# Power_ATX.net
KiCad netlist of a schematic drawn in Altium Designer
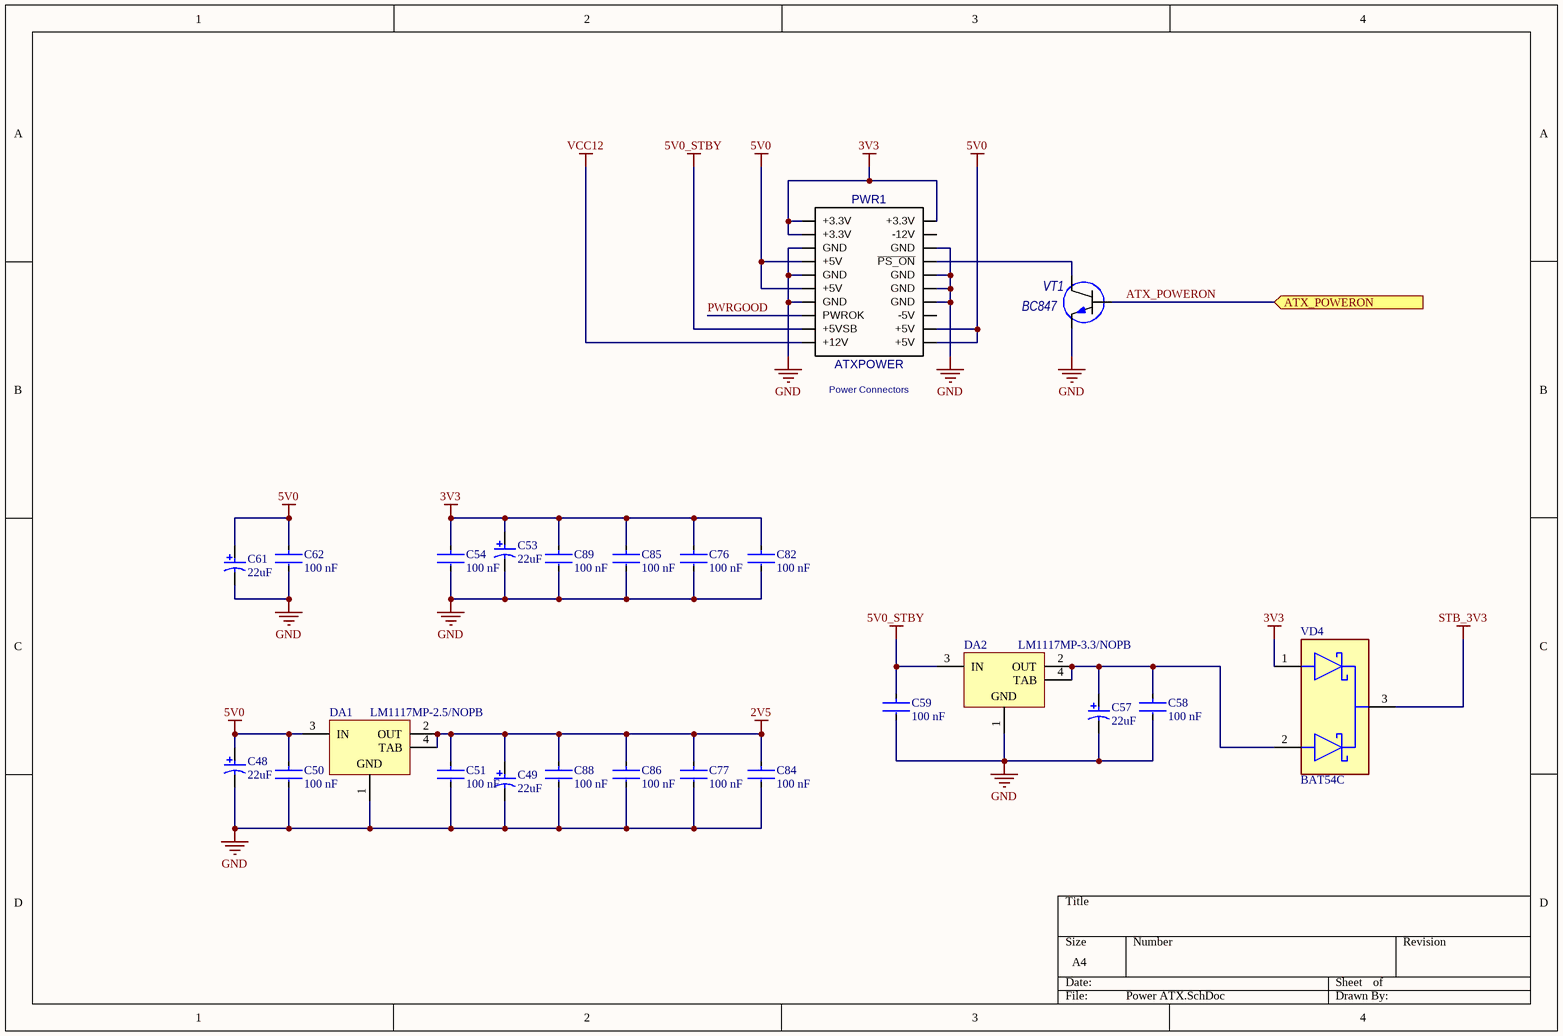
[diagram p0: Power ATX.SchDoc]

(export (version "E")
  (design (tool "Eeschema 10.0.6"))
  (components
    (comp (ref "C48")
      (value "TAJB226K016RNJ")
      (footprint "AVX-TAJ-B-2_M")
      (description "Standard Tantalum, 22 uF, +/- 10%, 16 V, -55 to 125 degC, 2-Pin SMD (1210), RoHS, Tape and Reel")
      (fields (field (name "CAPACITANCE") "22uF") (field (name "MANUFACTURER") "Kyocera AVX"))
      (libsource (lib "SchLib") (part "CMP-2100-03689-1"))
    )
    (comp (ref "C49")
      (value "TAJB226K016RNJ")
      (footprint "AVX-TAJ-B-2_M")
      (description "Standard Tantalum, 22 uF, +/- 10%, 16 V, -55 to 125 degC, 2-Pin SMD (1210), RoHS, Tape and Reel")
      (fields (field (name "CAPACITANCE") "22uF") (field (name "MANUFACTURER") "Kyocera AVX"))
      (libsource (lib "SchLib") (part "CMP-2100-03689-1"))
    )
    (comp (ref "C50")
      (value "CC0805KRX7R9BB104")
      (footprint "FP-CC0805-0_85-IPC_A")
      (description "CAP CER 0.1UF 50V X7R 0805")
      (fields (field (name "CAPACITANCE") "100 nF") (field (name "MANUFACTURER") "Yageo"))
      (libsource (lib "SchLib") (part "CMP-2100-03606-3"))
    )
    (comp (ref "C51")
      (value "CC0805KRX7R9BB104")
      (footprint "FP-CC0805-0_85-IPC_A")
      (description "CAP CER 0.1UF 50V X7R 0805")
      (fields (field (name "CAPACITANCE") "100 nF") (field (name "MANUFACTURER") "Yageo"))
      (libsource (lib "SchLib") (part "CMP-2100-03606-3"))
    )
    (comp (ref "C53")
      (value "TAJB226K016RNJ")
      (footprint "AVX-TAJ-B-2_M")
      (description "Standard Tantalum, 22 uF, +/- 10%, 16 V, -55 to 125 degC, 2-Pin SMD (1210), RoHS, Tape and Reel")
      (fields (field (name "CAPACITANCE") "22uF") (field (name "MANUFACTURER") "Kyocera AVX"))
      (libsource (lib "SchLib") (part "CMP-2100-03689-1"))
    )
    (comp (ref "C54")
      (value "CC0805KRX7R9BB104")
      (footprint "FP-CC0805-0_85-IPC_A")
      (description "CAP CER 0.1UF 50V X7R 0805")
      (fields (field (name "CAPACITANCE") "100 nF") (field (name "MANUFACTURER") "Yageo"))
      (libsource (lib "SchLib") (part "CMP-2100-03606-3"))
    )
    (comp (ref "C57")
      (value "TAJB226K016RNJ")
      (footprint "AVX-TAJ-B-2_M")
      (description "Standard Tantalum, 22 uF, +/- 10%, 16 V, -55 to 125 degC, 2-Pin SMD (1210), RoHS, Tape and Reel")
      (fields (field (name "CAPACITANCE") "22uF") (field (name "MANUFACTURER") "Kyocera AVX"))
      (libsource (lib "SchLib") (part "CMP-2100-03689-1"))
    )
    (comp (ref "C58")
      (value "CC0805KRX7R9BB104")
      (footprint "FP-CC0805-0_85-IPC_A")
      (description "CAP CER 0.1UF 50V X7R 0805")
      (fields (field (name "MANUFACTURER") "Yageo") (field (name "CAPACITANCE") "100 nF"))
      (libsource (lib "SchLib") (part "CMP-2100-03606-3"))
    )
    (comp (ref "C59")
      (value "CC0805KRX7R9BB104")
      (footprint "FP-CC0805-0_85-IPC_A")
      (description "CAP CER 0.1UF 50V X7R 0805")
      (fields (field (name "MANUFACTURER") "Yageo") (field (name "CAPACITANCE") "100 nF"))
      (libsource (lib "SchLib") (part "CMP-2100-03606-3"))
    )
    (comp (ref "C61")
      (value "TAJB226K016RNJ")
      (footprint "AVX-TAJ-B-2_M")
      (description "Standard Tantalum, 22 uF, +/- 10%, 16 V, -55 to 125 degC, 2-Pin SMD (1210), RoHS, Tape and Reel")
      (fields (field (name "CAPACITANCE") "22uF") (field (name "MANUFACTURER") "Kyocera AVX"))
      (libsource (lib "SchLib") (part "CMP-2100-03689-1"))
    )
    (comp (ref "C62")
      (value "CC0805KRX7R9BB104")
      (footprint "FP-CC0805-0_85-IPC_A")
      (description "CAP CER 0.1UF 50V X7R 0805")
      (fields (field (name "CAPACITANCE") "100 nF") (field (name "MANUFACTURER") "Yageo"))
      (libsource (lib "SchLib") (part "CMP-2100-03606-3"))
    )
    (comp (ref "C76")
      (value "CC0805KRX7R9BB104")
      (footprint "FP-CC0805-0_85-IPC_A")
      (description "CAP CER 0.1UF 50V X7R 0805")
      (fields (field (name "CAPACITANCE") "100 nF") (field (name "MANUFACTURER") "Yageo"))
      (libsource (lib "SchLib") (part "CMP-2100-03606-3"))
    )
    (comp (ref "C77")
      (value "CC0805KRX7R9BB104")
      (footprint "FP-CC0805-0_85-IPC_A")
      (description "CAP CER 0.1UF 50V X7R 0805")
      (fields (field (name "CAPACITANCE") "100 nF") (field (name "MANUFACTURER") "Yageo"))
      (libsource (lib "SchLib") (part "CMP-2100-03606-3"))
    )
    (comp (ref "C82")
      (value "CC0805KRX7R9BB104")
      (footprint "FP-CC0805-0_85-IPC_A")
      (description "CAP CER 0.1UF 50V X7R 0805")
      (fields (field (name "CAPACITANCE") "100 nF") (field (name "MANUFACTURER") "Yageo"))
      (libsource (lib "SchLib") (part "CMP-2100-03606-3"))
    )
    (comp (ref "C84")
      (value "CC0805KRX7R9BB104")
      (footprint "FP-CC0805-0_85-IPC_A")
      (description "CAP CER 0.1UF 50V X7R 0805")
      (fields (field (name "CAPACITANCE") "100 nF") (field (name "MANUFACTURER") "Yageo"))
      (libsource (lib "SchLib") (part "CMP-2100-03606-3"))
    )
    (comp (ref "C85")
      (value "CC0805KRX7R9BB104")
      (footprint "FP-CC0805-0_85-IPC_A")
      (description "CAP CER 0.1UF 50V X7R 0805")
      (fields (field (name "CAPACITANCE") "100 nF") (field (name "MANUFACTURER") "Yageo"))
      (libsource (lib "SchLib") (part "CMP-2100-03606-3"))
    )
    (comp (ref "C86")
      (value "CC0805KRX7R9BB104")
      (footprint "FP-CC0805-0_85-IPC_A")
      (description "CAP CER 0.1UF 50V X7R 0805")
      (fields (field (name "CAPACITANCE") "100 nF") (field (name "MANUFACTURER") "Yageo"))
      (libsource (lib "SchLib") (part "CMP-2100-03606-3"))
    )
    (comp (ref "C88")
      (value "CC0805KRX7R9BB104")
      (footprint "FP-CC0805-0_85-IPC_A")
      (description "CAP CER 0.1UF 50V X7R 0805")
      (fields (field (name "CAPACITANCE") "100 nF") (field (name "MANUFACTURER") "Yageo"))
      (libsource (lib "SchLib") (part "CMP-2100-03606-3"))
    )
    (comp (ref "C89")
      (value "CC0805KRX7R9BB104")
      (footprint "FP-CC0805-0_85-IPC_A")
      (description "CAP CER 0.1UF 50V X7R 0805")
      (fields (field (name "CAPACITANCE") "100 nF") (field (name "MANUFACTURER") "Yageo"))
      (libsource (lib "SchLib") (part "CMP-2100-03606-3"))
    )
    (comp (ref "DA1")
      (value "LM1117MP-2.5/NOPB")
      (footprint "DCY0004A_M")
      (description "800mA Low-Dropout Linear Regulator, 4-pin SOT-223, Pb-Free")
      (fields (field (name "MANUFACTURER") "TI National Semiconductor"))
      (libsource (lib "SchLib") (part "CMP-0062-01660-4"))
    )
    (comp (ref "DA2")
      (value "LM1117MP-3.3/NOPB")
      (footprint "DCY0004A_L")
      (description "800mA Low-Dropout Linear Regulator, 4-pin SOT-223, Pb-Free")
      (fields (field (name "MANUFACTURER") "TI National Semiconductor"))
      (libsource (lib "SchLib") (part "CMP-0062-01638-4"))
    )
    (comp (ref "PWR1") (value "ATXPOWER") (footprint "ATXPOWER") (libsource (lib "SchLib") (part "ATXPOWER")))
    (comp (ref "VD4")
      (value "BAT54C")
      (footprint "FP-MA03D-MFG")
      (description "DIODE ARRAY SCHOTTKY 30V SOT23-3")
      (fields (field (name "MANUFACTURER") "ON Semiconductor / Fairchild"))
      (libsource (lib "SchLib") (part "CMP-07162-000010-1"))
    )
    (comp (ref "VT1") (value "BC847") (footprint "SOT-23") (libsource (lib "SchLib") (part "BC847")))
  )
  (nets
    (net (code "1") (name "/ATX_POWERON") (class "Default")
      (node (ref "VT1") (pin "1") (pinfunction "base_1") (pintype "passive"))
    )
    (net (code "2") (name "/PWRGOOD") (class "Default")
      (node (ref "PWR1") (pin "8") (pinfunction "PWROK_8") (pintype "passive"))
    )
    (net (code "3") (name "2V5") (class "Default")
      (node (ref "C49") (pin "1") (pinfunction "1_1") (pintype "passive"))
      (node (ref "C51") (pin "1") (pinfunction "1_1") (pintype "passive"))
      (node (ref "C77") (pin "1") (pinfunction "1_1") (pintype "passive"))
      (node (ref "C84") (pin "1") (pinfunction "1_1") (pintype "passive"))
      (node (ref "C86") (pin "1") (pinfunction "1_1") (pintype "passive"))
      (node (ref "C88") (pin "1") (pinfunction "1_1") (pintype "passive"))
      (node (ref "DA1") (pin "2") (pinfunction "OUT_2") (pintype "power_in"))
      (node (ref "DA1") (pin "4") (pinfunction "TAB_4") (pintype "power_in"))
    )
    (net (code "4") (name "3V3") (class "Default")
      (node (ref "C53") (pin "1") (pinfunction "1_1") (pintype "passive"))
      (node (ref "C54") (pin "1") (pinfunction "1_1") (pintype "passive"))
      (node (ref "C76") (pin "1") (pinfunction "1_1") (pintype "passive"))
      (node (ref "C82") (pin "1") (pinfunction "1_1") (pintype "passive"))
      (node (ref "C85") (pin "1") (pinfunction "1_1") (pintype "passive"))
      (node (ref "C89") (pin "1") (pinfunction "1_1") (pintype "passive"))
      (node (ref "PWR1") (pin "1") (pinfunction "+3.3V_1") (pintype "passive"))
      (node (ref "PWR1") (pin "11") (pinfunction "+3.3V_11") (pintype "passive"))
      (node (ref "PWR1") (pin "2") (pinfunction "+3.3V_2") (pintype "passive"))
      (node (ref "VD4") (pin "1") (pinfunction "1_ANODE_1") (pintype "passive"))
    )
    (net (code "5") (name "5V0") (class "Default")
      (node (ref "C48") (pin "1") (pinfunction "1_1") (pintype "passive"))
      (node (ref "C50") (pin "1") (pinfunction "1_1") (pintype "passive"))
      (node (ref "C61") (pin "1") (pinfunction "1_1") (pintype "passive"))
      (node (ref "C62") (pin "1") (pinfunction "1_1") (pintype "passive"))
      (node (ref "DA1") (pin "3") (pinfunction "IN_3") (pintype "power_in"))
      (node (ref "PWR1") (pin "19") (pinfunction "+5V_19") (pintype "passive"))
      (node (ref "PWR1") (pin "20") (pinfunction "+5V_20") (pintype "passive"))
      (node (ref "PWR1") (pin "4") (pinfunction "+5V_4") (pintype "passive"))
      (node (ref "PWR1") (pin "6") (pinfunction "+5V_6") (pintype "passive"))
    )
    (net (code "6") (name "5V0_STBY") (class "Default")
      (node (ref "C59") (pin "1") (pinfunction "1_1") (pintype "passive"))
      (node (ref "DA2") (pin "3") (pinfunction "IN_3") (pintype "power_in"))
      (node (ref "PWR1") (pin "9") (pinfunction "+5VSB_9") (pintype "passive"))
    )
    (net (code "7") (name "GND") (class "Default")
      (node (ref "C48") (pin "2") (pinfunction "2_2") (pintype "passive"))
      (node (ref "C49") (pin "2") (pinfunction "2_2") (pintype "passive"))
      (node (ref "C50") (pin "2") (pinfunction "2_2") (pintype "passive"))
      (node (ref "C51") (pin "2") (pinfunction "2_2") (pintype "passive"))
      (node (ref "C53") (pin "2") (pinfunction "2_2") (pintype "passive"))
      (node (ref "C54") (pin "2") (pinfunction "2_2") (pintype "passive"))
      (node (ref "C57") (pin "2") (pinfunction "2_2") (pintype "passive"))
      (node (ref "C58") (pin "2") (pinfunction "2_2") (pintype "passive"))
      (node (ref "C59") (pin "2") (pinfunction "2_2") (pintype "passive"))
      (node (ref "C61") (pin "2") (pinfunction "2_2") (pintype "passive"))
      (node (ref "C62") (pin "2") (pinfunction "2_2") (pintype "passive"))
      (node (ref "C76") (pin "2") (pinfunction "2_2") (pintype "passive"))
      (node (ref "C77") (pin "2") (pinfunction "2_2") (pintype "passive"))
      (node (ref "C82") (pin "2") (pinfunction "2_2") (pintype "passive"))
      (node (ref "C84") (pin "2") (pinfunction "2_2") (pintype "passive"))
      (node (ref "C85") (pin "2") (pinfunction "2_2") (pintype "passive"))
      (node (ref "C86") (pin "2") (pinfunction "2_2") (pintype "passive"))
      (node (ref "C88") (pin "2") (pinfunction "2_2") (pintype "passive"))
      (node (ref "C89") (pin "2") (pinfunction "2_2") (pintype "passive"))
      (node (ref "DA1") (pin "1") (pinfunction "GND_1") (pintype "power_in"))
      (node (ref "DA2") (pin "1") (pinfunction "GND_1") (pintype "power_in"))
      (node (ref "PWR1") (pin "13") (pinfunction "GND_13") (pintype "passive"))
      (node (ref "PWR1") (pin "15") (pinfunction "GND_15") (pintype "passive"))
      (node (ref "PWR1") (pin "16") (pinfunction "GND_16") (pintype "passive"))
      (node (ref "PWR1") (pin "17") (pinfunction "GND_17") (pintype "passive"))
      (node (ref "PWR1") (pin "3") (pinfunction "GND_3") (pintype "passive"))
      (node (ref "PWR1") (pin "5") (pinfunction "GND_5") (pintype "passive"))
      (node (ref "PWR1") (pin "7") (pinfunction "GND_7") (pintype "passive"))
      (node (ref "VT1") (pin "2") (pinfunction "emitter_2") (pintype "passive"))
    )
    (net (code "8") (name "Net-(DA2-OUT)") (class "Default")
      (node (ref "C57") (pin "1") (pinfunction "1_1") (pintype "passive"))
      (node (ref "C58") (pin "1") (pinfunction "1_1") (pintype "passive"))
      (node (ref "DA2") (pin "2") (pinfunction "OUT_2") (pintype "power_in"))
      (node (ref "DA2") (pin "4") (pinfunction "TAB_4") (pintype "power_in"))
      (node (ref "VD4") (pin "2") (pinfunction "2_ANODE_2") (pintype "passive"))
    )
    (net (code "9") (name "Net-(PWR1-~{PS_ON})") (class "Default")
      (node (ref "PWR1") (pin "14") (pinfunction "~{PS_ON}_14") (pintype "passive"))
      (node (ref "VT1") (pin "3") (pinfunction "collector_3") (pintype "passive"))
    )
    (net (code "10") (name "STB_3V3") (class "Default")
      (node (ref "VD4") (pin "3") (pinfunction "COMMON_CATHODE_3") (pintype "passive"))
    )
    (net (code "11") (name "VCC12") (class "Default")
      (node (ref "PWR1") (pin "10") (pinfunction "+12V_10") (pintype "passive"))
    )
    (net (code "12") (name "unconnected-(PWR1--5V-Pad18)") (class "Default")
      (node (ref "PWR1") (pin "18") (pinfunction "-5V_18") (pintype "passive"))
    )
    (net (code "13") (name "unconnected-(PWR1--12V-Pad12)") (class "Default")
      (node (ref "PWR1") (pin "12") (pinfunction "-12V_12") (pintype "passive"))
    )
  )
)
